# Audio-Beamformer_Driver_V1_0.net
KiCad netlist of a schematic drawn in Altium Designer
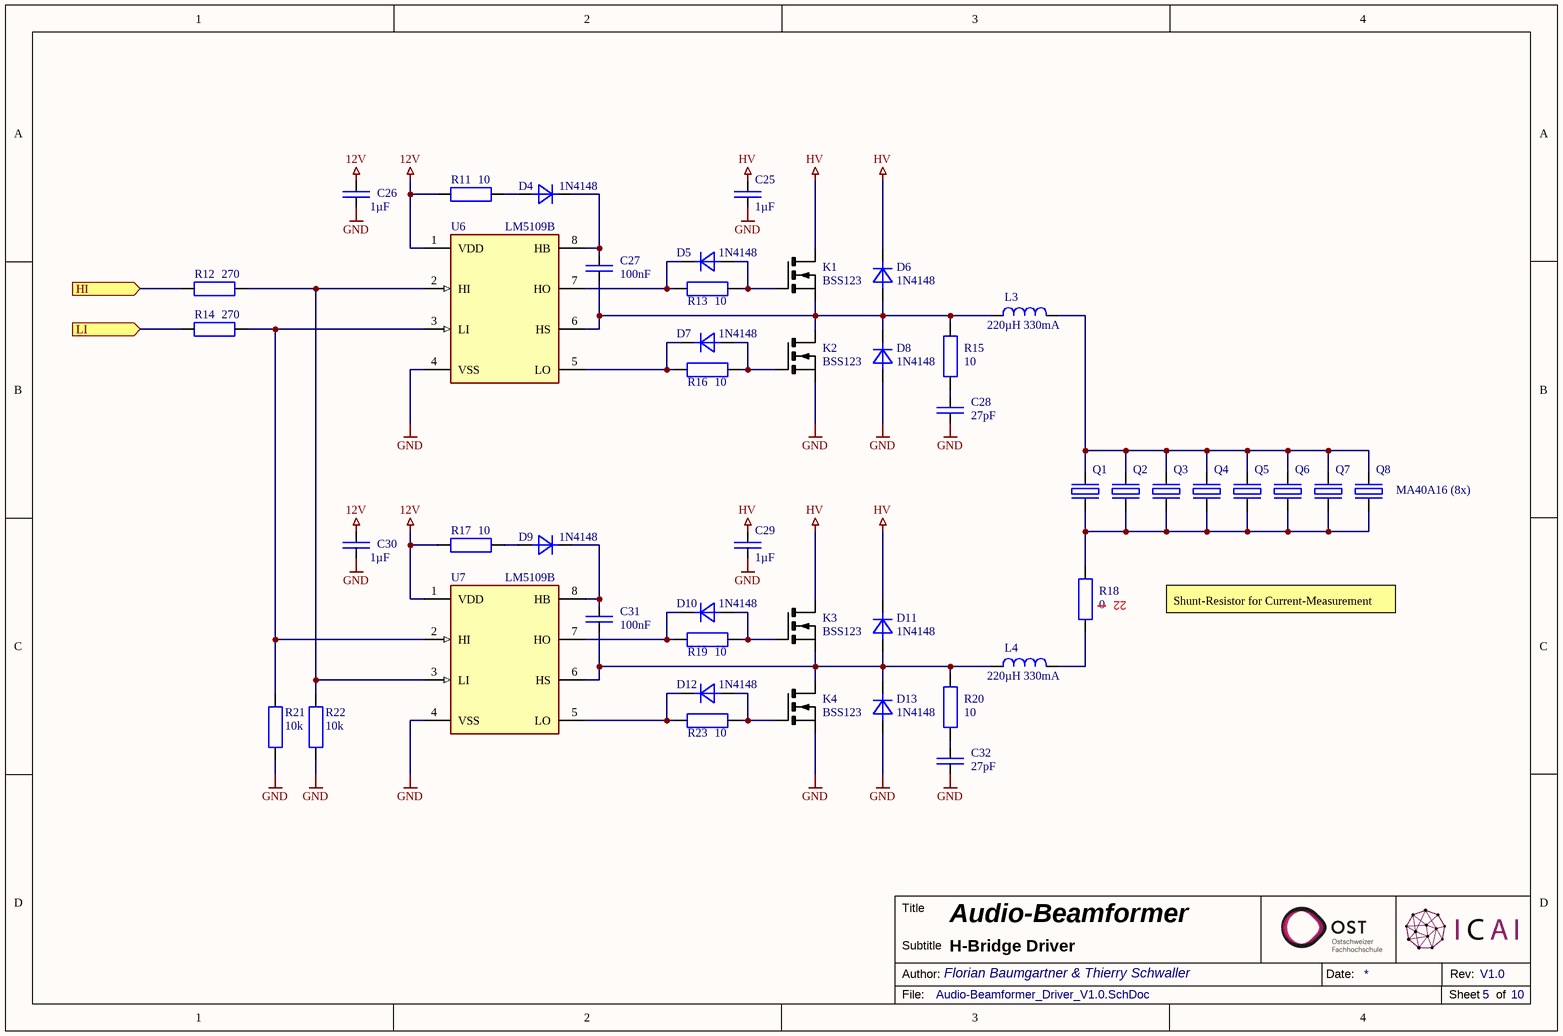
[diagram p0: Audio-Beamformer_Driver_V1.0.SchDoc]

(export (version "E")
  (design (tool "Eeschema 10.0.6"))
  (components
    (comp (ref "C25")
      (value "1µF")
      (footprint "SMD Keramikkondensator 1206")
      (description "CAP-MK")
      (libsource (lib "AudioAmp") (part "C-CAPACITOR"))
    )
    (comp (ref "C26")
      (value "1µF")
      (footprint "SMD Keramikkondensator 0603")
      (description "CAP-MK")
      (libsource (lib "AudioAmp") (part "C-CAPACITOR"))
    )
    (comp (ref "C27")
      (value "100nF")
      (footprint "SMD Keramikkondensator 0603")
      (description "CAP-MK")
      (libsource (lib "AudioAmp") (part "C-CAPACITOR"))
    )
    (comp (ref "C28")
      (value "27pF")
      (footprint "SMD Keramikkondensator 0603")
      (description "CAP-MK")
      (libsource (lib "AudioAmp") (part "C-CAPACITOR"))
    )
    (comp (ref "C29")
      (value "1µF")
      (footprint "SMD Keramikkondensator 1206")
      (description "CAP-MK")
      (libsource (lib "AudioAmp") (part "C-CAPACITOR"))
    )
    (comp (ref "C30")
      (value "1µF")
      (footprint "SMD Keramikkondensator 0603")
      (description "CAP-MK")
      (libsource (lib "AudioAmp") (part "C-CAPACITOR"))
    )
    (comp (ref "C31")
      (value "100nF")
      (footprint "SMD Keramikkondensator 0603")
      (description "CAP-MK")
      (libsource (lib "AudioAmp") (part "C-CAPACITOR"))
    )
    (comp (ref "C32")
      (value "27pF")
      (footprint "SMD Keramikkondensator 0603")
      (description "CAP-MK")
      (libsource (lib "AudioAmp") (part "C-CAPACITOR"))
    )
    (comp (ref "D4")
      (value "1N4148")
      (footprint "SMD Diode SOD-123")
      (description "DIODE (alt V)")
      (libsource (lib "TFS Integrated Library") (part "R-DIODE"))
    )
    (comp (ref "D5")
      (value "1N4148")
      (footprint "SMD Diode SOD-123")
      (description "DIODE (alt V)")
      (libsource (lib "TFS Integrated Library") (part "R-DIODE"))
    )
    (comp (ref "D6")
      (value "1N4148")
      (footprint "SMD Diode SOD-123")
      (description "DIODE (alt V)")
      (libsource (lib "TFS Integrated Library") (part "R-DIODE"))
    )
    (comp (ref "D7")
      (value "1N4148")
      (footprint "SMD Diode SOD-123")
      (description "DIODE (alt V)")
      (libsource (lib "TFS Integrated Library") (part "R-DIODE"))
    )
    (comp (ref "D8")
      (value "1N4148")
      (footprint "SMD Diode SOD-123")
      (description "DIODE (alt V)")
      (libsource (lib "TFS Integrated Library") (part "R-DIODE"))
    )
    (comp (ref "D9")
      (value "1N4148")
      (footprint "SMD Diode SOD-123")
      (description "DIODE (alt V)")
      (libsource (lib "TFS Integrated Library") (part "R-DIODE"))
    )
    (comp (ref "D10")
      (value "1N4148")
      (footprint "SMD Diode SOD-123")
      (description "DIODE (alt V)")
      (libsource (lib "TFS Integrated Library") (part "R-DIODE"))
    )
    (comp (ref "D11")
      (value "1N4148")
      (footprint "SMD Diode SOD-123")
      (description "DIODE (alt V)")
      (libsource (lib "TFS Integrated Library") (part "R-DIODE"))
    )
    (comp (ref "D12")
      (value "1N4148")
      (footprint "SMD Diode SOD-123")
      (description "DIODE (alt V)")
      (libsource (lib "TFS Integrated Library") (part "R-DIODE"))
    )
    (comp (ref "D13")
      (value "1N4148")
      (footprint "SMD Diode SOD-123")
      (description "DIODE (alt V)")
      (libsource (lib "TFS Integrated Library") (part "R-DIODE"))
    )
    (comp (ref "K1")
      (value "BSS123")
      (footprint "SMD MOSFET SOT-23")
      (description "MOSFET N-Channel")
      (libsource (lib "Nixie-Test") (part "K-FET{colon}NIGE"))
    )
    (comp (ref "K2")
      (value "BSS123")
      (footprint "SMD MOSFET SOT-23")
      (description "MOSFET N-Channel")
      (libsource (lib "Nixie-Test") (part "K-FET{colon}NIGE"))
    )
    (comp (ref "K3")
      (value "BSS123")
      (footprint "SMD MOSFET SOT-23")
      (description "MOSFET N-Channel")
      (libsource (lib "Nixie-Test") (part "K-FET{colon}NIGE"))
    )
    (comp (ref "K4")
      (value "BSS123")
      (footprint "SMD MOSFET SOT-23")
      (description "MOSFET N-Channel")
      (libsource (lib "Nixie-Test") (part "K-FET{colon}NIGE"))
    )
    (comp (ref "L3")
      (value "220µH 330mA")
      (footprint "SMD Inductor 7x7x4.5")
      (description "Shielded Power Inductor")
      (libsource (lib "Nixie-Test") (part "L-COIL"))
    )
    (comp (ref "L4")
      (value "220µH 330mA")
      (footprint "SMD Inductor 7x7x4.5")
      (description "Shielded Power Inductor")
      (libsource (lib "Nixie-Test") (part "L-COIL"))
    )
    (comp (ref "Q1")
      (value "MA40A16")
      (footprint "THT Transducer (MA40A16) (5mm Offset)")
      (description "Ultrasonic Transducer")
      (libsource (lib "Quad-Stage-Prototype") (part "Q-Piezo"))
    )
    (comp (ref "Q2")
      (value "MA40A16")
      (footprint "THT Transducer (MA40A16) (5mm Offset)")
      (description "Ultrasonic Transducer")
      (libsource (lib "Quad-Stage-Prototype") (part "Q-Piezo"))
    )
    (comp (ref "Q3")
      (value "MA40A16")
      (footprint "THT Transducer (MA40A16) (5mm Offset)")
      (description "Ultrasonic Transducer")
      (libsource (lib "Quad-Stage-Prototype") (part "Q-Piezo"))
    )
    (comp (ref "Q4")
      (value "MA40A16")
      (footprint "THT Transducer (MA40A16) (5mm Offset)")
      (description "Ultrasonic Transducer")
      (libsource (lib "Quad-Stage-Prototype") (part "Q-Piezo"))
    )
    (comp (ref "Q5")
      (value "MA40A16")
      (footprint "THT Transducer (MA40A16) (5mm Offset)")
      (description "Ultrasonic Transducer")
      (libsource (lib "Quad-Stage-Prototype") (part "Q-Piezo"))
    )
    (comp (ref "Q6")
      (value "MA40A16")
      (footprint "THT Transducer (MA40A16) (5mm Offset)")
      (description "Ultrasonic Transducer")
      (libsource (lib "Quad-Stage-Prototype") (part "Q-Piezo"))
    )
    (comp (ref "Q7")
      (value "MA40A16")
      (footprint "THT Transducer (MA40A16) (5mm Offset)")
      (description "Ultrasonic Transducer")
      (libsource (lib "Quad-Stage-Prototype") (part "Q-Piezo"))
    )
    (comp (ref "Q8")
      (value "MA40A16")
      (footprint "THT Transducer (MA40A16) (5mm Offset)")
      (description "Ultrasonic Transducer")
      (libsource (lib "Quad-Stage-Prototype") (part "Q-Piezo"))
    )
    (comp (ref "R11")
      (value "10")
      (footprint "SMD Widerstand 0603")
      (description "RES (E=Heizwiderstand B=Messwandler)")
      (libsource (lib "") (part "R-RESISTOR_1"))
    )
    (comp (ref "R12")
      (value "270")
      (footprint "SMD Widerstand 0603")
      (description "SMD-Widerstand 1/4W")
      (libsource (lib "Backplane_1") (part "R-RESISTOR"))
    )
    (comp (ref "R13")
      (value "10")
      (footprint "SMD Widerstand 0603")
      (description "RES (E=Heizwiderstand B=Messwandler)")
      (libsource (lib "") (part "R-RESISTOR_1"))
    )
    (comp (ref "R14")
      (value "270")
      (footprint "SMD Widerstand 0603")
      (description "SMD-Widerstand 1/4W")
      (libsource (lib "Backplane_1") (part "R-RESISTOR"))
    )
    (comp (ref "R15")
      (value "10")
      (footprint "SMD Widerstand 1206")
      (description "RES (E=Heizwiderstand B=Messwandler)")
      (libsource (lib "TFS Integrated Library") (part "R-RESISTOR"))
    )
    (comp (ref "R16")
      (value "10")
      (footprint "SMD Widerstand 0603")
      (description "RES (E=Heizwiderstand B=Messwandler)")
      (libsource (lib "") (part "R-RESISTOR_1"))
    )
    (comp (ref "R17")
      (value "10")
      (footprint "SMD Widerstand 0603")
      (description "RES (E=Heizwiderstand B=Messwandler)")
      (libsource (lib "") (part "R-RESISTOR_1"))
    )
    (comp (ref "R18")
      (value "0")
      (footprint "SMD Widerstand 1206")
      (description "RES (E=Heizwiderstand B=Messwandler)")
      (libsource (lib "TFS Integrated Library") (part "R-RESISTOR"))
    )
    (comp (ref "R19")
      (value "10")
      (footprint "SMD Widerstand 0603")
      (description "RES (E=Heizwiderstand B=Messwandler)")
      (libsource (lib "") (part "R-RESISTOR_1"))
    )
    (comp (ref "R20")
      (value "10")
      (footprint "SMD Widerstand 1206")
      (description "RES (E=Heizwiderstand B=Messwandler)")
      (libsource (lib "TFS Integrated Library") (part "R-RESISTOR"))
    )
    (comp (ref "R21")
      (value "10k")
      (footprint "SMD Widerstand 0603")
      (description "RES (E=Heizwiderstand B=Messwandler)")
      (libsource (lib "TFS Integrated Library") (part "R-RESISTOR"))
    )
    (comp (ref "R22")
      (value "10k")
      (footprint "SMD Widerstand 0603")
      (description "RES (E=Heizwiderstand B=Messwandler)")
      (libsource (lib "TFS Integrated Library") (part "R-RESISTOR"))
    )
    (comp (ref "R23")
      (value "10")
      (footprint "SMD Widerstand 0603")
      (description "RES (E=Heizwiderstand B=Messwandler)")
      (libsource (lib "") (part "R-RESISTOR_1"))
    )
    (comp (ref "U6")
      (value "LM5109B")
      (footprint "SMD IC SOIC-8")
      (description "High Voltage 1A Peak Half Bridge Gate Driver")
      (libsource (lib "Quad-Stage-Prototype") (part "U-LM5109B"))
    )
    (comp (ref "U7")
      (value "LM5109B")
      (footprint "SMD IC SOIC-8")
      (description "High Voltage 1A Peak Half Bridge Gate Driver")
      (libsource (lib "Quad-Stage-Prototype") (part "U-LM5109B"))
    )
  )
  (nets
    (net (code "1") (name "/HI") (class "Default")
      (node (ref "R12") (pin "1") (pinfunction "1_1") (pintype "passive"))
    )
    (net (code "2") (name "/LI") (class "Default")
      (node (ref "R14") (pin "1") (pinfunction "1_1") (pintype "passive"))
    )
    (net (code "3") (name "12V") (class "Default")
      (node (ref "C26") (pin "2") (pinfunction "2_2") (pintype "passive"))
      (node (ref "C30") (pin "2") (pinfunction "2_2") (pintype "passive"))
      (node (ref "R11") (pin "2") (pinfunction "2_2") (pintype "passive"))
      (node (ref "R17") (pin "2") (pinfunction "2_2") (pintype "passive"))
      (node (ref "U6") (pin "1") (pinfunction "VDD_1") (pintype "power_in"))
      (node (ref "U7") (pin "1") (pinfunction "VDD_1") (pintype "power_in"))
    )
    (net (code "4") (name "GND") (class "Default")
      (node (ref "C25") (pin "1") (pinfunction "1_1") (pintype "passive"))
      (node (ref "C26") (pin "1") (pinfunction "1_1") (pintype "passive"))
      (node (ref "C28") (pin "2") (pinfunction "2_2") (pintype "passive"))
      (node (ref "C29") (pin "1") (pinfunction "1_1") (pintype "passive"))
      (node (ref "C30") (pin "1") (pinfunction "1_1") (pintype "passive"))
      (node (ref "C32") (pin "2") (pinfunction "2_2") (pintype "passive"))
      (node (ref "D13") (pin "A") (pinfunction "A_A") (pintype "passive"))
      (node (ref "D8") (pin "A") (pinfunction "A_A") (pintype "passive"))
      (node (ref "K2") (pin "S") (pinfunction "S_S") (pintype "passive"))
      (node (ref "K4") (pin "S") (pinfunction "S_S") (pintype "passive"))
      (node (ref "R21") (pin "1") (pinfunction "1_1") (pintype "passive"))
      (node (ref "R22") (pin "1") (pinfunction "1_1") (pintype "passive"))
      (node (ref "U6") (pin "4") (pinfunction "VSS_4") (pintype "power_in"))
      (node (ref "U7") (pin "4") (pinfunction "VSS_4") (pintype "power_in"))
    )
    (net (code "5") (name "HV") (class "Default")
      (node (ref "C25") (pin "2") (pinfunction "2_2") (pintype "passive"))
      (node (ref "C29") (pin "2") (pinfunction "2_2") (pintype "passive"))
      (node (ref "D11") (pin "K") (pinfunction "K_K") (pintype "passive"))
      (node (ref "D6") (pin "K") (pinfunction "K_K") (pintype "passive"))
      (node (ref "K1") (pin "D") (pinfunction "D_D") (pintype "passive"))
      (node (ref "K3") (pin "D") (pinfunction "D_D") (pintype "passive"))
    )
    (net (code "6") (name "Net-(C28-Pad1)") (class "Default")
      (node (ref "C28") (pin "1") (pinfunction "1_1") (pintype "passive"))
      (node (ref "R15") (pin "1") (pinfunction "1_1") (pintype "passive"))
    )
    (net (code "7") (name "Net-(C32-Pad1)") (class "Default")
      (node (ref "C32") (pin "1") (pinfunction "1_1") (pintype "passive"))
      (node (ref "R20") (pin "1") (pinfunction "1_1") (pintype "passive"))
    )
    (net (code "8") (name "Net-(D4-PadA)") (class "Default")
      (node (ref "D4") (pin "A") (pinfunction "A_A") (pintype "passive"))
      (node (ref "R11") (pin "1") (pinfunction "1_1") (pintype "passive"))
    )
    (net (code "9") (name "Net-(D5-PadA)") (class "Default")
      (node (ref "D5") (pin "A") (pinfunction "A_A") (pintype "passive"))
      (node (ref "K1") (pin "G") (pinfunction "G_G") (pintype "passive"))
      (node (ref "R13") (pin "1") (pinfunction "1_1") (pintype "passive"))
    )
    (net (code "10") (name "Net-(D7-PadA)") (class "Default")
      (node (ref "D7") (pin "A") (pinfunction "A_A") (pintype "passive"))
      (node (ref "K2") (pin "G") (pinfunction "G_G") (pintype "passive"))
      (node (ref "R16") (pin "1") (pinfunction "1_1") (pintype "passive"))
    )
    (net (code "11") (name "Net-(D9-PadA)") (class "Default")
      (node (ref "D9") (pin "A") (pinfunction "A_A") (pintype "passive"))
      (node (ref "R17") (pin "1") (pinfunction "1_1") (pintype "passive"))
    )
    (net (code "12") (name "Net-(D10-PadA)") (class "Default")
      (node (ref "D10") (pin "A") (pinfunction "A_A") (pintype "passive"))
      (node (ref "K3") (pin "G") (pinfunction "G_G") (pintype "passive"))
      (node (ref "R19") (pin "1") (pinfunction "1_1") (pintype "passive"))
    )
    (net (code "13") (name "Net-(D12-PadA)") (class "Default")
      (node (ref "D12") (pin "A") (pinfunction "A_A") (pintype "passive"))
      (node (ref "K4") (pin "G") (pinfunction "G_G") (pintype "passive"))
      (node (ref "R23") (pin "1") (pinfunction "1_1") (pintype "passive"))
    )
    (net (code "14") (name "Net-(L3-Pad2)") (class "Default")
      (node (ref "L3") (pin "2") (pinfunction "2_2") (pintype "passive"))
      (node (ref "Q1") (pin "2") (pinfunction "2_2") (pintype "passive"))
      (node (ref "Q2") (pin "2") (pinfunction "2_2") (pintype "passive"))
      (node (ref "Q3") (pin "2") (pinfunction "2_2") (pintype "passive"))
      (node (ref "Q4") (pin "2") (pinfunction "2_2") (pintype "passive"))
      (node (ref "Q5") (pin "2") (pinfunction "2_2") (pintype "passive"))
      (node (ref "Q6") (pin "2") (pinfunction "2_2") (pintype "passive"))
      (node (ref "Q7") (pin "2") (pinfunction "2_2") (pintype "passive"))
      (node (ref "Q8") (pin "2") (pinfunction "2_2") (pintype "passive"))
    )
    (net (code "15") (name "Net-(L4-Pad2)") (class "Default")
      (node (ref "L4") (pin "2") (pinfunction "2_2") (pintype "passive"))
      (node (ref "R18") (pin "1") (pinfunction "1_1") (pintype "passive"))
    )
    (net (code "16") (name "Net-(Q1-Pad1)") (class "Default")
      (node (ref "Q1") (pin "1") (pinfunction "1_1") (pintype "passive"))
      (node (ref "Q2") (pin "1") (pinfunction "1_1") (pintype "passive"))
      (node (ref "Q3") (pin "1") (pinfunction "1_1") (pintype "passive"))
      (node (ref "Q4") (pin "1") (pinfunction "1_1") (pintype "passive"))
      (node (ref "Q5") (pin "1") (pinfunction "1_1") (pintype "passive"))
      (node (ref "Q6") (pin "1") (pinfunction "1_1") (pintype "passive"))
      (node (ref "Q7") (pin "1") (pinfunction "1_1") (pintype "passive"))
      (node (ref "Q8") (pin "1") (pinfunction "1_1") (pintype "passive"))
      (node (ref "R18") (pin "2") (pinfunction "2_2") (pintype "passive"))
    )
    (net (code "17") (name "Net-(U6-HB)") (class "Default")
      (node (ref "C27") (pin "2") (pinfunction "2_2") (pintype "passive"))
      (node (ref "D4") (pin "K") (pinfunction "K_K") (pintype "passive"))
      (node (ref "U6") (pin "8") (pinfunction "HB_8") (pintype "passive"))
    )
    (net (code "18") (name "Net-(U6-HI)") (class "Default")
      (node (ref "R12") (pin "2") (pinfunction "2_2") (pintype "passive"))
      (node (ref "R22") (pin "2") (pinfunction "2_2") (pintype "passive"))
      (node (ref "U6") (pin "2") (pinfunction "HI_2") (pintype "input"))
      (node (ref "U7") (pin "3") (pinfunction "LI_3") (pintype "input"))
    )
    (net (code "19") (name "Net-(U6-HO)") (class "Default")
      (node (ref "D5") (pin "K") (pinfunction "K_K") (pintype "passive"))
      (node (ref "R13") (pin "2") (pinfunction "2_2") (pintype "passive"))
      (node (ref "U6") (pin "7") (pinfunction "HO_7") (pintype "passive"))
    )
    (net (code "20") (name "Net-(U6-HS)") (class "Default")
      (node (ref "C27") (pin "1") (pinfunction "1_1") (pintype "passive"))
      (node (ref "D6") (pin "A") (pinfunction "A_A") (pintype "passive"))
      (node (ref "D8") (pin "K") (pinfunction "K_K") (pintype "passive"))
      (node (ref "K1") (pin "S") (pinfunction "S_S") (pintype "passive"))
      (node (ref "K2") (pin "D") (pinfunction "D_D") (pintype "passive"))
      (node (ref "L3") (pin "1") (pinfunction "1_1") (pintype "passive"))
      (node (ref "R15") (pin "2") (pinfunction "2_2") (pintype "passive"))
      (node (ref "U6") (pin "6") (pinfunction "HS_6") (pintype "passive"))
    )
    (net (code "21") (name "Net-(U6-LI)") (class "Default")
      (node (ref "R14") (pin "2") (pinfunction "2_2") (pintype "passive"))
      (node (ref "R21") (pin "2") (pinfunction "2_2") (pintype "passive"))
      (node (ref "U6") (pin "3") (pinfunction "LI_3") (pintype "input"))
      (node (ref "U7") (pin "2") (pinfunction "HI_2") (pintype "input"))
    )
    (net (code "22") (name "Net-(U6-LO)") (class "Default")
      (node (ref "D7") (pin "K") (pinfunction "K_K") (pintype "passive"))
      (node (ref "R16") (pin "2") (pinfunction "2_2") (pintype "passive"))
      (node (ref "U6") (pin "5") (pinfunction "LO_5") (pintype "passive"))
    )
    (net (code "23") (name "Net-(U7-HB)") (class "Default")
      (node (ref "C31") (pin "2") (pinfunction "2_2") (pintype "passive"))
      (node (ref "D9") (pin "K") (pinfunction "K_K") (pintype "passive"))
      (node (ref "U7") (pin "8") (pinfunction "HB_8") (pintype "passive"))
    )
    (net (code "24") (name "Net-(U7-HO)") (class "Default")
      (node (ref "D10") (pin "K") (pinfunction "K_K") (pintype "passive"))
      (node (ref "R19") (pin "2") (pinfunction "2_2") (pintype "passive"))
      (node (ref "U7") (pin "7") (pinfunction "HO_7") (pintype "passive"))
    )
    (net (code "25") (name "Net-(U7-HS)") (class "Default")
      (node (ref "C31") (pin "1") (pinfunction "1_1") (pintype "passive"))
      (node (ref "D11") (pin "A") (pinfunction "A_A") (pintype "passive"))
      (node (ref "D13") (pin "K") (pinfunction "K_K") (pintype "passive"))
      (node (ref "K3") (pin "S") (pinfunction "S_S") (pintype "passive"))
      (node (ref "K4") (pin "D") (pinfunction "D_D") (pintype "passive"))
      (node (ref "L4") (pin "1") (pinfunction "1_1") (pintype "passive"))
      (node (ref "R20") (pin "2") (pinfunction "2_2") (pintype "passive"))
      (node (ref "U7") (pin "6") (pinfunction "HS_6") (pintype "passive"))
    )
    (net (code "26") (name "Net-(U7-LO)") (class "Default")
      (node (ref "D12") (pin "K") (pinfunction "K_K") (pintype "passive"))
      (node (ref "R23") (pin "2") (pinfunction "2_2") (pintype "passive"))
      (node (ref "U7") (pin "5") (pinfunction "LO_5") (pintype "passive"))
    )
  )
)
